# 01_ZYNQ_DDR.net
KiCad netlist of a schematic drawn in Altium Designer
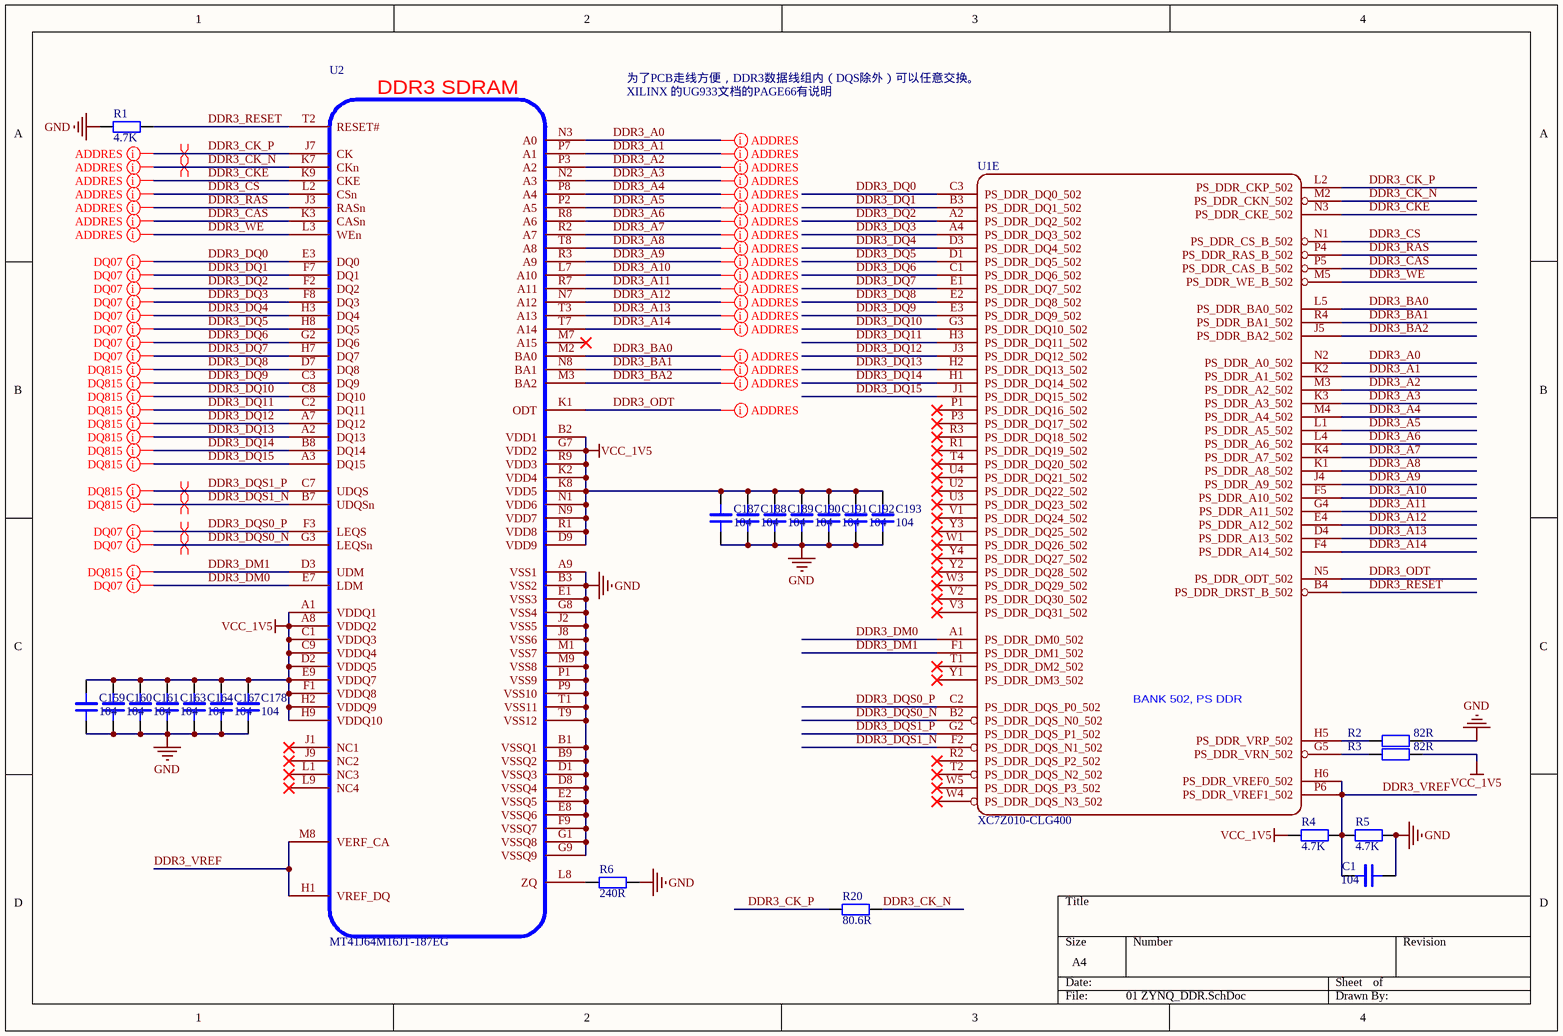
[diagram p0: 01 ZYNQ_DDR.SchDoc]

(export (version "E")
  (design (tool "Eeschema 10.0.6"))
  (components
    (comp (ref "C1")
      (value "104")
      (footprint "LC-0402_C")
      (description "Capacitor")
      (libsource (lib "General") (part "CAP"))
    )
    (comp (ref "C159")
      (value "104")
      (footprint "LC-0402_C")
      (description "Capacitor")
      (libsource (lib "General") (part "CAP"))
    )
    (comp (ref "C160")
      (value "104")
      (footprint "LC-0402_C")
      (description "Capacitor")
      (libsource (lib "General") (part "CAP"))
    )
    (comp (ref "C161")
      (value "104")
      (footprint "LC-0402_C")
      (description "Capacitor")
      (libsource (lib "General") (part "CAP"))
    )
    (comp (ref "C163")
      (value "104")
      (footprint "LC-0402_C")
      (description "Capacitor")
      (libsource (lib "General") (part "CAP"))
    )
    (comp (ref "C164")
      (value "104")
      (footprint "LC-0402_C")
      (description "Capacitor")
      (libsource (lib "General") (part "CAP"))
    )
    (comp (ref "C167")
      (value "104")
      (footprint "LC-0402_C")
      (description "Capacitor")
      (libsource (lib "General") (part "CAP"))
    )
    (comp (ref "C178")
      (value "104")
      (footprint "LC-0402_C")
      (description "Capacitor")
      (libsource (lib "General") (part "CAP"))
    )
    (comp (ref "C187")
      (value "104")
      (footprint "LC-0402_C")
      (description "Capacitor")
      (libsource (lib "General") (part "CAP"))
    )
    (comp (ref "C188")
      (value "104")
      (footprint "LC-0402_C")
      (description "Capacitor")
      (libsource (lib "General") (part "CAP"))
    )
    (comp (ref "C189")
      (value "104")
      (footprint "LC-0402_C")
      (description "Capacitor")
      (libsource (lib "General") (part "CAP"))
    )
    (comp (ref "C190")
      (value "104")
      (footprint "LC-0402_C")
      (description "Capacitor")
      (libsource (lib "General") (part "CAP"))
    )
    (comp (ref "C191")
      (value "104")
      (footprint "LC-0402_C")
      (description "Capacitor")
      (libsource (lib "General") (part "CAP"))
    )
    (comp (ref "C192")
      (value "104")
      (footprint "LC-0402_C")
      (description "Capacitor")
      (libsource (lib "General") (part "CAP"))
    )
    (comp (ref "C193")
      (value "104")
      (footprint "LC-0402_C")
      (description "Capacitor")
      (libsource (lib "General") (part "CAP"))
    )
    (comp (ref "R1")
      (value "4.7K")
      (footprint "LC-0402_R")
      (description "Resistor")
      (libsource (lib "General") (part "RES"))
    )
    (comp (ref "R2")
      (value "82R")
      (footprint "LC-0402_R")
      (description "Resistor")
      (libsource (lib "General") (part "RES"))
    )
    (comp (ref "R3")
      (value "82R")
      (footprint "LC-0402_R")
      (description "Resistor")
      (libsource (lib "General") (part "RES"))
    )
    (comp (ref "R4")
      (value "4.7K")
      (footprint "LC-0402_R")
      (description "Resistor")
      (libsource (lib "General") (part "RES"))
    )
    (comp (ref "R5")
      (value "4.7K")
      (footprint "LC-0402_R")
      (description "Resistor")
      (libsource (lib "General") (part "RES"))
    )
    (comp (ref "R6")
      (value "240R")
      (footprint "LC-0402_R")
      (description "Resistor")
      (libsource (lib "") (part "RES_1"))
    )
    (comp (ref "R20")
      (value "80.6R")
      (footprint "LC-0402_R")
      (description "Resistor")
      (libsource (lib "") (part "RES_1"))
    )
    (comp (ref "U1")
      (value "XC7Z010-CLG400")
      (footprint "CLG400-0.8")
      (libsource (lib "DDR3_xc7z010-clg400") (part "XC7Z010-CLG400"))
    )
    (comp (ref "U2")
      (value "MT41J64M16JT-187EG")
      (footprint "FBGA96")
      (libsource (lib "DDR3_xc7z010-clg400") (part "DDR3"))
    )
  )
  (nets
    (net (code "1") (name "/DDR3_A0") (class "Default")
      (node (ref "U1") (pin "N2") (pinfunction "PS_DDR_A0_502_N2") (pintype "passive"))
      (node (ref "U2") (pin "N3") (pinfunction "A0_N3") (pintype "passive"))
    )
    (net (code "2") (name "/DDR3_A1") (class "Default")
      (node (ref "U1") (pin "K2") (pinfunction "PS_DDR_A1_502_K2") (pintype "passive"))
      (node (ref "U2") (pin "P7") (pinfunction "A1_P7") (pintype "passive"))
    )
    (net (code "3") (name "/DDR3_A2") (class "Default")
      (node (ref "U1") (pin "M3") (pinfunction "PS_DDR_A2_502_M3") (pintype "passive"))
      (node (ref "U2") (pin "P3") (pinfunction "A2_P3") (pintype "passive"))
    )
    (net (code "4") (name "/DDR3_A3") (class "Default")
      (node (ref "U1") (pin "K3") (pinfunction "PS_DDR_A3_502_K3") (pintype "passive"))
      (node (ref "U2") (pin "N2") (pinfunction "A3_N2") (pintype "passive"))
    )
    (net (code "5") (name "/DDR3_A4") (class "Default")
      (node (ref "U1") (pin "M4") (pinfunction "PS_DDR_A4_502_M4") (pintype "passive"))
      (node (ref "U2") (pin "P8") (pinfunction "A4_P8") (pintype "passive"))
    )
    (net (code "6") (name "/DDR3_A5") (class "Default")
      (node (ref "U1") (pin "L1") (pinfunction "PS_DDR_A5_502_L1") (pintype "passive"))
      (node (ref "U2") (pin "P2") (pinfunction "A5_P2") (pintype "passive"))
    )
    (net (code "7") (name "/DDR3_A6") (class "Default")
      (node (ref "U1") (pin "L4") (pinfunction "PS_DDR_A6_502_L4") (pintype "passive"))
      (node (ref "U2") (pin "R8") (pinfunction "A6_R8") (pintype "passive"))
    )
    (net (code "8") (name "/DDR3_A7") (class "Default")
      (node (ref "U1") (pin "K4") (pinfunction "PS_DDR_A7_502_K4") (pintype "passive"))
      (node (ref "U2") (pin "R2") (pinfunction "A7_R2") (pintype "passive"))
    )
    (net (code "9") (name "/DDR3_A8") (class "Default")
      (node (ref "U1") (pin "K1") (pinfunction "PS_DDR_A8_502_K1") (pintype "passive"))
      (node (ref "U2") (pin "T8") (pinfunction "A8_T8") (pintype "passive"))
    )
    (net (code "10") (name "/DDR3_A9") (class "Default")
      (node (ref "U1") (pin "J4") (pinfunction "PS_DDR_A9_502_J4") (pintype "passive"))
      (node (ref "U2") (pin "R3") (pinfunction "A9_R3") (pintype "passive"))
    )
    (net (code "11") (name "/DDR3_A10") (class "Default")
      (node (ref "U1") (pin "F5") (pinfunction "PS_DDR_A10_502_F5") (pintype "passive"))
      (node (ref "U2") (pin "L7") (pinfunction "A10_L7") (pintype "passive"))
    )
    (net (code "12") (name "/DDR3_A11") (class "Default")
      (node (ref "U1") (pin "G4") (pinfunction "PS_DDR_A11_502_G4") (pintype "passive"))
      (node (ref "U2") (pin "R7") (pinfunction "A11_R7") (pintype "passive"))
    )
    (net (code "13") (name "/DDR3_A12") (class "Default")
      (node (ref "U1") (pin "E4") (pinfunction "PS_DDR_A12_502_E4") (pintype "passive"))
      (node (ref "U2") (pin "N7") (pinfunction "A12_N7") (pintype "passive"))
    )
    (net (code "14") (name "/DDR3_A13") (class "Default")
      (node (ref "U1") (pin "D4") (pinfunction "PS_DDR_A13_502_D4") (pintype "passive"))
      (node (ref "U2") (pin "T3") (pinfunction "A13_T3") (pintype "passive"))
    )
    (net (code "15") (name "/DDR3_A14") (class "Default")
      (node (ref "U1") (pin "F4") (pinfunction "PS_DDR_A14_502_F4") (pintype "passive"))
      (node (ref "U2") (pin "T7") (pinfunction "A14_T7") (pintype "passive"))
    )
    (net (code "16") (name "/DDR3_BA0") (class "Default")
      (node (ref "U1") (pin "L5") (pinfunction "PS_DDR_BA0_502_L5") (pintype "passive"))
      (node (ref "U2") (pin "M2") (pinfunction "BA0_M2") (pintype "passive"))
    )
    (net (code "17") (name "/DDR3_BA1") (class "Default")
      (node (ref "U1") (pin "R4") (pinfunction "PS_DDR_BA1_502_R4") (pintype "passive"))
      (node (ref "U2") (pin "N8") (pinfunction "BA1_N8") (pintype "passive"))
    )
    (net (code "18") (name "/DDR3_BA2") (class "Default")
      (node (ref "U1") (pin "J5") (pinfunction "PS_DDR_BA2_502_J5") (pintype "passive"))
      (node (ref "U2") (pin "M3") (pinfunction "BA2_M3") (pintype "passive"))
    )
    (net (code "19") (name "/DDR3_CAS") (class "Default")
      (node (ref "U1") (pin "P5") (pinfunction "PS_DDR_CAS_B_502_P5") (pintype "passive"))
      (node (ref "U2") (pin "K3") (pinfunction "CASn_K3") (pintype "passive"))
    )
    (net (code "20") (name "/DDR3_CKE") (class "Default")
      (node (ref "U1") (pin "N3") (pinfunction "PS_DDR_CKE_502_N3") (pintype "passive"))
      (node (ref "U2") (pin "K9") (pinfunction "CKE_K9") (pintype "passive"))
    )
    (net (code "21") (name "/DDR3_CK_N") (class "Default")
      (node (ref "R20") (pin "2") (pinfunction "2_2") (pintype "passive"))
      (node (ref "U1") (pin "M2") (pinfunction "PS_DDR_CKN_502_M2") (pintype "passive"))
      (node (ref "U2") (pin "K7") (pinfunction "CKn_K7") (pintype "passive"))
    )
    (net (code "22") (name "/DDR3_CK_P") (class "Default")
      (node (ref "R20") (pin "1") (pinfunction "1_1") (pintype "passive"))
      (node (ref "U1") (pin "L2") (pinfunction "PS_DDR_CKP_502_L2") (pintype "passive"))
      (node (ref "U2") (pin "J7") (pinfunction "CK_J7") (pintype "passive"))
    )
    (net (code "23") (name "/DDR3_CS") (class "Default")
      (node (ref "U1") (pin "N1") (pinfunction "PS_DDR_CS_B_502_N1") (pintype "passive"))
      (node (ref "U2") (pin "L2") (pinfunction "CSn_L2") (pintype "passive"))
    )
    (net (code "24") (name "/DDR3_DM0") (class "Default")
      (node (ref "U1") (pin "A1") (pinfunction "PS_DDR_DM0_502_A1") (pintype "passive"))
      (node (ref "U2") (pin "E7") (pinfunction "LDM_E7") (pintype "passive"))
    )
    (net (code "25") (name "/DDR3_DM1") (class "Default")
      (node (ref "U1") (pin "F1") (pinfunction "PS_DDR_DM1_502_F1") (pintype "passive"))
      (node (ref "U2") (pin "D3") (pinfunction "UDM_D3") (pintype "passive"))
    )
    (net (code "26") (name "/DDR3_DQ0") (class "Default")
      (node (ref "U1") (pin "C3") (pinfunction "PS_DDR_DQ0_502_C3") (pintype "passive"))
      (node (ref "U2") (pin "E3") (pinfunction "DQ0_E3") (pintype "passive"))
    )
    (net (code "27") (name "/DDR3_DQ1") (class "Default")
      (node (ref "U1") (pin "B3") (pinfunction "PS_DDR_DQ1_502_B3") (pintype "passive"))
      (node (ref "U2") (pin "F7") (pinfunction "DQ1_F7") (pintype "passive"))
    )
    (net (code "28") (name "/DDR3_DQ2") (class "Default")
      (node (ref "U1") (pin "A2") (pinfunction "PS_DDR_DQ2_502_A2") (pintype "passive"))
      (node (ref "U2") (pin "F2") (pinfunction "DQ2_F2") (pintype "passive"))
    )
    (net (code "29") (name "/DDR3_DQ3") (class "Default")
      (node (ref "U1") (pin "A4") (pinfunction "PS_DDR_DQ3_502_A4") (pintype "passive"))
      (node (ref "U2") (pin "F8") (pinfunction "DQ3_F8") (pintype "passive"))
    )
    (net (code "30") (name "/DDR3_DQ4") (class "Default")
      (node (ref "U1") (pin "D3") (pinfunction "PS_DDR_DQ4_502_D3") (pintype "passive"))
      (node (ref "U2") (pin "H3") (pinfunction "DQ4_H3") (pintype "passive"))
    )
    (net (code "31") (name "/DDR3_DQ5") (class "Default")
      (node (ref "U1") (pin "D1") (pinfunction "PS_DDR_DQ5_502_D1") (pintype "passive"))
      (node (ref "U2") (pin "H8") (pinfunction "DQ5_H8") (pintype "passive"))
    )
    (net (code "32") (name "/DDR3_DQ6") (class "Default")
      (node (ref "U1") (pin "C1") (pinfunction "PS_DDR_DQ6_502_C1") (pintype "passive"))
      (node (ref "U2") (pin "G2") (pinfunction "DQ6_G2") (pintype "passive"))
    )
    (net (code "33") (name "/DDR3_DQ7") (class "Default")
      (node (ref "U1") (pin "E1") (pinfunction "PS_DDR_DQ7_502_E1") (pintype "passive"))
      (node (ref "U2") (pin "H7") (pinfunction "DQ7_H7") (pintype "passive"))
    )
    (net (code "34") (name "/DDR3_DQ8") (class "Default")
      (node (ref "U1") (pin "E2") (pinfunction "PS_DDR_DQ8_502_E2") (pintype "passive"))
      (node (ref "U2") (pin "D7") (pinfunction "DQ8_D7") (pintype "passive"))
    )
    (net (code "35") (name "/DDR3_DQ9") (class "Default")
      (node (ref "U1") (pin "E3") (pinfunction "PS_DDR_DQ9_502_E3") (pintype "passive"))
      (node (ref "U2") (pin "C3") (pinfunction "DQ9_C3") (pintype "passive"))
    )
    (net (code "36") (name "/DDR3_DQ10") (class "Default")
      (node (ref "U1") (pin "G3") (pinfunction "PS_DDR_DQ10_502_G3") (pintype "passive"))
      (node (ref "U2") (pin "C8") (pinfunction "DQ10_C8") (pintype "passive"))
    )
    (net (code "37") (name "/DDR3_DQ11") (class "Default")
      (node (ref "U1") (pin "H3") (pinfunction "PS_DDR_DQ11_502_H3") (pintype "passive"))
      (node (ref "U2") (pin "C2") (pinfunction "DQ11_C2") (pintype "passive"))
    )
    (net (code "38") (name "/DDR3_DQ12") (class "Default")
      (node (ref "U1") (pin "J3") (pinfunction "PS_DDR_DQ12_502_J3") (pintype "passive"))
      (node (ref "U2") (pin "A7") (pinfunction "DQ12_A7") (pintype "passive"))
    )
    (net (code "39") (name "/DDR3_DQ13") (class "Default")
      (node (ref "U1") (pin "H2") (pinfunction "PS_DDR_DQ13_502_H2") (pintype "passive"))
      (node (ref "U2") (pin "A2") (pinfunction "DQ13_A2") (pintype "passive"))
    )
    (net (code "40") (name "/DDR3_DQ14") (class "Default")
      (node (ref "U1") (pin "H1") (pinfunction "PS_DDR_DQ14_502_H1") (pintype "passive"))
      (node (ref "U2") (pin "B8") (pinfunction "DQ14_B8") (pintype "passive"))
    )
    (net (code "41") (name "/DDR3_DQ15") (class "Default")
      (node (ref "U1") (pin "J1") (pinfunction "PS_DDR_DQ15_502_J1") (pintype "passive"))
      (node (ref "U2") (pin "A3") (pinfunction "DQ15_A3") (pintype "passive"))
    )
    (net (code "42") (name "/DDR3_DQS0_N") (class "Default")
      (node (ref "U1") (pin "B2") (pinfunction "PS_DDR_DQS_N0_502_B2") (pintype "passive"))
      (node (ref "U2") (pin "G3") (pinfunction "LEQSn_G3") (pintype "passive"))
    )
    (net (code "43") (name "/DDR3_DQS0_P") (class "Default")
      (node (ref "U1") (pin "C2") (pinfunction "PS_DDR_DQS_P0_502_C2") (pintype "passive"))
      (node (ref "U2") (pin "F3") (pinfunction "LEQS_F3") (pintype "passive"))
    )
    (net (code "44") (name "/DDR3_DQS1_N") (class "Default")
      (node (ref "U1") (pin "F2") (pinfunction "PS_DDR_DQS_N1_502_F2") (pintype "passive"))
      (node (ref "U2") (pin "B7") (pinfunction "UDQSn_B7") (pintype "passive"))
    )
    (net (code "45") (name "/DDR3_DQS1_P") (class "Default")
      (node (ref "U1") (pin "G2") (pinfunction "PS_DDR_DQS_P1_502_G2") (pintype "passive"))
      (node (ref "U2") (pin "C7") (pinfunction "UDQS_C7") (pintype "passive"))
    )
    (net (code "46") (name "/DDR3_ODT") (class "Default")
      (node (ref "U1") (pin "N5") (pinfunction "PS_DDR_ODT_502_N5") (pintype "passive"))
      (node (ref "U2") (pin "K1") (pinfunction "ODT_K1") (pintype "passive"))
    )
    (net (code "47") (name "/DDR3_RAS") (class "Default")
      (node (ref "U1") (pin "P4") (pinfunction "PS_DDR_RAS_B_502_P4") (pintype "passive"))
      (node (ref "U2") (pin "J3") (pinfunction "RASn_J3") (pintype "passive"))
    )
    (net (code "48") (name "/DDR3_RESET") (class "Default")
      (node (ref "R1") (pin "1") (pinfunction "1_1") (pintype "passive"))
      (node (ref "U1") (pin "B4") (pinfunction "PS_DDR_DRST_B_502_B4") (pintype "passive"))
      (node (ref "U2") (pin "T2") (pinfunction "RESET#_T2") (pintype "passive"))
    )
    (net (code "49") (name "/DDR3_VREF") (class "Default")
      (node (ref "C1") (pin "1") (pinfunction "1_1") (pintype "passive"))
      (node (ref "R4") (pin "1") (pinfunction "1_1") (pintype "passive"))
      (node (ref "R5") (pin "2") (pinfunction "2_2") (pintype "passive"))
      (node (ref "U1") (pin "H6") (pinfunction "PS_DDR_VREF0_502_H6") (pintype "passive"))
      (node (ref "U1") (pin "P6") (pinfunction "PS_DDR_VREF1_502_P6") (pintype "passive"))
      (node (ref "U2") (pin "H1") (pinfunction "VREF_DQ_H1") (pintype "passive"))
      (node (ref "U2") (pin "M8") (pinfunction "VERF_CA_M8") (pintype "passive"))
    )
    (net (code "50") (name "/DDR3_WE") (class "Default")
      (node (ref "U1") (pin "M5") (pinfunction "PS_DDR_WE_B_502_M5") (pintype "passive"))
      (node (ref "U2") (pin "L3") (pinfunction "WEn_L3") (pintype "passive"))
    )
    (net (code "51") (name "GND") (class "Default")
      (node (ref "C1") (pin "2") (pinfunction "2_2") (pintype "passive"))
      (node (ref "C159") (pin "1") (pinfunction "1_1") (pintype "passive"))
      (node (ref "C160") (pin "1") (pinfunction "1_1") (pintype "passive"))
      (node (ref "C161") (pin "1") (pinfunction "1_1") (pintype "passive"))
      (node (ref "C163") (pin "1") (pinfunction "1_1") (pintype "passive"))
      (node (ref "C164") (pin "1") (pinfunction "1_1") (pintype "passive"))
      (node (ref "C167") (pin "1") (pinfunction "1_1") (pintype "passive"))
      (node (ref "C178") (pin "1") (pinfunction "1_1") (pintype "passive"))
      (node (ref "C187") (pin "1") (pinfunction "1_1") (pintype "passive"))
      (node (ref "C188") (pin "1") (pinfunction "1_1") (pintype "passive"))
      (node (ref "C189") (pin "1") (pinfunction "1_1") (pintype "passive"))
      (node (ref "C190") (pin "1") (pinfunction "1_1") (pintype "passive"))
      (node (ref "C191") (pin "1") (pinfunction "1_1") (pintype "passive"))
      (node (ref "C192") (pin "1") (pinfunction "1_1") (pintype "passive"))
      (node (ref "C193") (pin "1") (pinfunction "1_1") (pintype "passive"))
      (node (ref "R1") (pin "2") (pinfunction "2_2") (pintype "passive"))
      (node (ref "R2") (pin "1") (pinfunction "1_1") (pintype "passive"))
      (node (ref "R5") (pin "1") (pinfunction "1_1") (pintype "passive"))
      (node (ref "R6") (pin "2") (pinfunction "2_2") (pintype "passive"))
      (node (ref "U2") (pin "A9") (pinfunction "VSS1_A9") (pintype "passive"))
      (node (ref "U2") (pin "B1") (pinfunction "VSSQ1_B1") (pintype "passive"))
      (node (ref "U2") (pin "B3") (pinfunction "VSS2_B3") (pintype "passive"))
      (node (ref "U2") (pin "B9") (pinfunction "VSSQ2_B9") (pintype "passive"))
      (node (ref "U2") (pin "D1") (pinfunction "VSSQ3_D1") (pintype "passive"))
      (node (ref "U2") (pin "D8") (pinfunction "VSSQ4_D8") (pintype "passive"))
      (node (ref "U2") (pin "E1") (pinfunction "VSS3_E1") (pintype "passive"))
      (node (ref "U2") (pin "E2") (pinfunction "VSSQ5_E2") (pintype "passive"))
      (node (ref "U2") (pin "E8") (pinfunction "VSSQ6_E8") (pintype "passive"))
      (node (ref "U2") (pin "F9") (pinfunction "VSSQ7_F9") (pintype "passive"))
      (node (ref "U2") (pin "G1") (pinfunction "VSSQ8_G1") (pintype "passive"))
      (node (ref "U2") (pin "G8") (pinfunction "VSS4_G8") (pintype "passive"))
      (node (ref "U2") (pin "G9") (pinfunction "VSSQ9_G9") (pintype "passive"))
      (node (ref "U2") (pin "J2") (pinfunction "VSS5_J2") (pintype "passive"))
      (node (ref "U2") (pin "J8") (pinfunction "VSS6_J8") (pintype "passive"))
      (node (ref "U2") (pin "M1") (pinfunction "VSS7_M1") (pintype "passive"))
      (node (ref "U2") (pin "M9") (pinfunction "VSS8_M9") (pintype "passive"))
      (node (ref "U2") (pin "P1") (pinfunction "VSS9_P1") (pintype "passive"))
      (node (ref "U2") (pin "P9") (pinfunction "VSS10_P9") (pintype "passive"))
      (node (ref "U2") (pin "T1") (pinfunction "VSS11_T1") (pintype "passive"))
      (node (ref "U2") (pin "T9") (pinfunction "VSS12_T9") (pintype "passive"))
    )
    (net (code "52") (name "Net-(U1E-PS_DDR_VRN_502)") (class "Default")
      (node (ref "R3") (pin "2") (pinfunction "2_2") (pintype "passive"))
      (node (ref "U1") (pin "G5") (pinfunction "PS_DDR_VRN_502_G5") (pintype "passive"))
    )
    (net (code "53") (name "Net-(U1E-PS_DDR_VRP_502)") (class "Default")
      (node (ref "R2") (pin "2") (pinfunction "2_2") (pintype "passive"))
      (node (ref "U1") (pin "H5") (pinfunction "PS_DDR_VRP_502_H5") (pintype "passive"))
    )
    (net (code "54") (name "Net-(U2-ZQ)") (class "Default")
      (node (ref "R6") (pin "1") (pinfunction "1_1") (pintype "passive"))
      (node (ref "U2") (pin "L8") (pinfunction "ZQ_L8") (pintype "passive"))
    )
    (net (code "55") (name "VCC_1V5") (class "Default")
      (node (ref "C159") (pin "2") (pinfunction "2_2") (pintype "passive"))
      (node (ref "C160") (pin "2") (pinfunction "2_2") (pintype "passive"))
      (node (ref "C161") (pin "2") (pinfunction "2_2") (pintype "passive"))
      (node (ref "C163") (pin "2") (pinfunction "2_2") (pintype "passive"))
      (node (ref "C164") (pin "2") (pinfunction "2_2") (pintype "passive"))
      (node (ref "C167") (pin "2") (pinfunction "2_2") (pintype "passive"))
      (node (ref "C178") (pin "2") (pinfunction "2_2") (pintype "passive"))
      (node (ref "C187") (pin "2") (pinfunction "2_2") (pintype "passive"))
      (node (ref "C188") (pin "2") (pinfunction "2_2") (pintype "passive"))
      (node (ref "C189") (pin "2") (pinfunction "2_2") (pintype "passive"))
      (node (ref "C190") (pin "2") (pinfunction "2_2") (pintype "passive"))
      (node (ref "C191") (pin "2") (pinfunction "2_2") (pintype "passive"))
      (node (ref "C192") (pin "2") (pinfunction "2_2") (pintype "passive"))
      (node (ref "C193") (pin "2") (pinfunction "2_2") (pintype "passive"))
      (node (ref "R3") (pin "1") (pinfunction "1_1") (pintype "passive"))
      (node (ref "R4") (pin "2") (pinfunction "2_2") (pintype "passive"))
      (node (ref "U2") (pin "A1") (pinfunction "VDDQ1_A1") (pintype "passive"))
      (node (ref "U2") (pin "A8") (pinfunction "VDDQ2_A8") (pintype "passive"))
      (node (ref "U2") (pin "B2") (pinfunction "VDD1_B2") (pintype "passive"))
      (node (ref "U2") (pin "C1") (pinfunction "VDDQ3_C1") (pintype "passive"))
      (node (ref "U2") (pin "C9") (pinfunction "VDDQ4_C9") (pintype "passive"))
      (node (ref "U2") (pin "D2") (pinfunction "VDDQ5_D2") (pintype "passive"))
      (node (ref "U2") (pin "D9") (pinfunction "VDD9_D9") (pintype "passive"))
      (node (ref "U2") (pin "E9") (pinfunction "VDDQ7_E9") (pintype "passive"))
      (node (ref "U2") (pin "F1") (pinfunction "VDDQ8_F1") (pintype "passive"))
      (node (ref "U2") (pin "G7") (pinfunction "VDD2_G7") (pintype "passive"))
      (node (ref "U2") (pin "H2") (pinfunction "VDDQ9_H2") (pintype "passive"))
      (node (ref "U2") (pin "H9") (pinfunction "VDDQ10_H9") (pintype "passive"))
      (node (ref "U2") (pin "K2") (pinfunction "VDD4_K2") (pintype "passive"))
      (node (ref "U2") (pin "K8") (pinfunction "VDD5_K8") (pintype "passive"))
      (node (ref "U2") (pin "N1") (pinfunction "VDD6_N1") (pintype "passive"))
      (node (ref "U2") (pin "N9") (pinfunction "VDD7_N9") (pintype "passive"))
      (node (ref "U2") (pin "R1") (pinfunction "VDD8_R1") (pintype "passive"))
      (node (ref "U2") (pin "R9") (pinfunction "VDD3_R9") (pintype "passive"))
    )
    (net (code "56") (name "unconnected-(U1E-PS_DDR_DM2_502-PadT1)") (class "Default")
      (node (ref "U1") (pin "T1") (pinfunction "PS_DDR_DM2_502_T1") (pintype "passive+no_connect"))
    )
    (net (code "57") (name "unconnected-(U1E-PS_DDR_DM3_502-PadY1)") (class "Default")
      (node (ref "U1") (pin "Y1") (pinfunction "PS_DDR_DM3_502_Y1") (pintype "passive+no_connect"))
    )
    (net (code "58") (name "unconnected-(U1E-PS_DDR_DQ16_502-PadP1)") (class "Default")
      (node (ref "U1") (pin "P1") (pinfunction "PS_DDR_DQ16_502_P1") (pintype "passive+no_connect"))
    )
    (net (code "59") (name "unconnected-(U1E-PS_DDR_DQ17_502-PadP3)") (class "Default")
      (node (ref "U1") (pin "P3") (pinfunction "PS_DDR_DQ17_502_P3") (pintype "passive+no_connect"))
    )
    (net (code "60") (name "unconnected-(U1E-PS_DDR_DQ18_502-PadR3)") (class "Default")
      (node (ref "U1") (pin "R3") (pinfunction "PS_DDR_DQ18_502_R3") (pintype "passive+no_connect"))
    )
    (net (code "61") (name "unconnected-(U1E-PS_DDR_DQ19_502-PadR1)") (class "Default")
      (node (ref "U1") (pin "R1") (pinfunction "PS_DDR_DQ19_502_R1") (pintype "passive+no_connect"))
    )
    (net (code "62") (name "unconnected-(U1E-PS_DDR_DQ20_502-PadT4)") (class "Default")
      (node (ref "U1") (pin "T4") (pinfunction "PS_DDR_DQ20_502_T4") (pintype "passive+no_connect"))
    )
    (net (code "63") (name "unconnected-(U1E-PS_DDR_DQ21_502-PadU4)") (class "Default")
      (node (ref "U1") (pin "U4") (pinfunction "PS_DDR_DQ21_502_U4") (pintype "passive+no_connect"))
    )
    (net (code "64") (name "unconnected-(U1E-PS_DDR_DQ22_502-PadU2)") (class "Default")
      (node (ref "U1") (pin "U2") (pinfunction "PS_DDR_DQ22_502_U2") (pintype "passive+no_connect"))
    )
    (net (code "65") (name "unconnected-(U1E-PS_DDR_DQ23_502-PadU3)") (class "Default")
      (node (ref "U1") (pin "U3") (pinfunction "PS_DDR_DQ23_502_U3") (pintype "passive+no_connect"))
    )
    (net (code "66") (name "unconnected-(U1E-PS_DDR_DQ24_502-PadV1)") (class "Default")
      (node (ref "U1") (pin "V1") (pinfunction "PS_DDR_DQ24_502_V1") (pintype "passive+no_connect"))
    )
    (net (code "67") (name "unconnected-(U1E-PS_DDR_DQ25_502-PadY3)") (class "Default")
      (node (ref "U1") (pin "Y3") (pinfunction "PS_DDR_DQ25_502_Y3") (pintype "passive+no_connect"))
    )
    (net (code "68") (name "unconnected-(U1E-PS_DDR_DQ26_502-PadW1)") (class "Default")
      (node (ref "U1") (pin "W1") (pinfunction "PS_DDR_DQ26_502_W1") (pintype "passive+no_connect"))
    )
    (net (code "69") (name "unconnected-(U1E-PS_DDR_DQ27_502-PadY4)") (class "Default")
      (node (ref "U1") (pin "Y4") (pinfunction "PS_DDR_DQ27_502_Y4") (pintype "passive+no_connect"))
    )
    (net (code "70") (name "unconnected-(U1E-PS_DDR_DQ28_502-PadY2)") (class "Default")
      (node (ref "U1") (pin "Y2") (pinfunction "PS_DDR_DQ28_502_Y2") (pintype "passive+no_connect"))
    )
    (net (code "71") (name "unconnected-(U1E-PS_DDR_DQ29_502-PadW3)") (class "Default")
      (node (ref "U1") (pin "W3") (pinfunction "PS_DDR_DQ29_502_W3") (pintype "passive+no_connect"))
    )
    (net (code "72") (name "unconnected-(U1E-PS_DDR_DQ30_502-PadV2)") (class "Default")
      (node (ref "U1") (pin "V2") (pinfunction "PS_DDR_DQ30_502_V2") (pintype "passive+no_connect"))
    )
    (net (code "73") (name "unconnected-(U1E-PS_DDR_DQ31_502-PadV3)") (class "Default")
      (node (ref "U1") (pin "V3") (pinfunction "PS_DDR_DQ31_502_V3") (pintype "passive+no_connect"))
    )
    (net (code "74") (name "unconnected-(U1E-PS_DDR_DQS_N2_502-PadT2)") (class "Default")
      (node (ref "U1") (pin "T2") (pinfunction "PS_DDR_DQS_N2_502_T2") (pintype "passive+no_connect"))
    )
    (net (code "75") (name "unconnected-(U1E-PS_DDR_DQS_N3_502-PadW4)") (class "Default")
      (node (ref "U1") (pin "W4") (pinfunction "PS_DDR_DQS_N3_502_W4") (pintype "passive+no_connect"))
    )
    (net (code "76") (name "unconnected-(U1E-PS_DDR_DQS_P2_502-PadR2)") (class "Default")
      (node (ref "U1") (pin "R2") (pinfunction "PS_DDR_DQS_P2_502_R2") (pintype "passive+no_connect"))
    )
    (net (code "77") (name "unconnected-(U1E-PS_DDR_DQS_P3_502-PadW5)") (class "Default")
      (node (ref "U1") (pin "W5") (pinfunction "PS_DDR_DQS_P3_502_W5") (pintype "passive+no_connect"))
    )
    (net (code "78") (name "unconnected-(U2-A15-PadM7)") (class "Default")
      (node (ref "U2") (pin "M7") (pinfunction "A15_M7") (pintype "passive+no_connect"))
    )
    (net (code "79") (name "unconnected-(U2-NC1-PadJ1)") (class "Default")
      (node (ref "U2") (pin "J1") (pinfunction "NC1_J1") (pintype "passive+no_connect"))
    )
    (net (code "80") (name "unconnected-(U2-NC2-PadJ9)") (class "Default")
      (node (ref "U2") (pin "J9") (pinfunction "NC2_J9") (pintype "passive+no_connect"))
    )
    (net (code "81") (name "unconnected-(U2-NC3-PadL1)") (class "Default")
      (node (ref "U2") (pin "L1") (pinfunction "NC3_L1") (pintype "passive+no_connect"))
    )
    (net (code "82") (name "unconnected-(U2-NC4-PadL9)") (class "Default")
      (node (ref "U2") (pin "L9") (pinfunction "NC4_L9") (pintype "passive+no_connect"))
    )
  )
)
